# 555LEDBLINK.net
KiCad netlist of a schematic drawn in Altium Designer
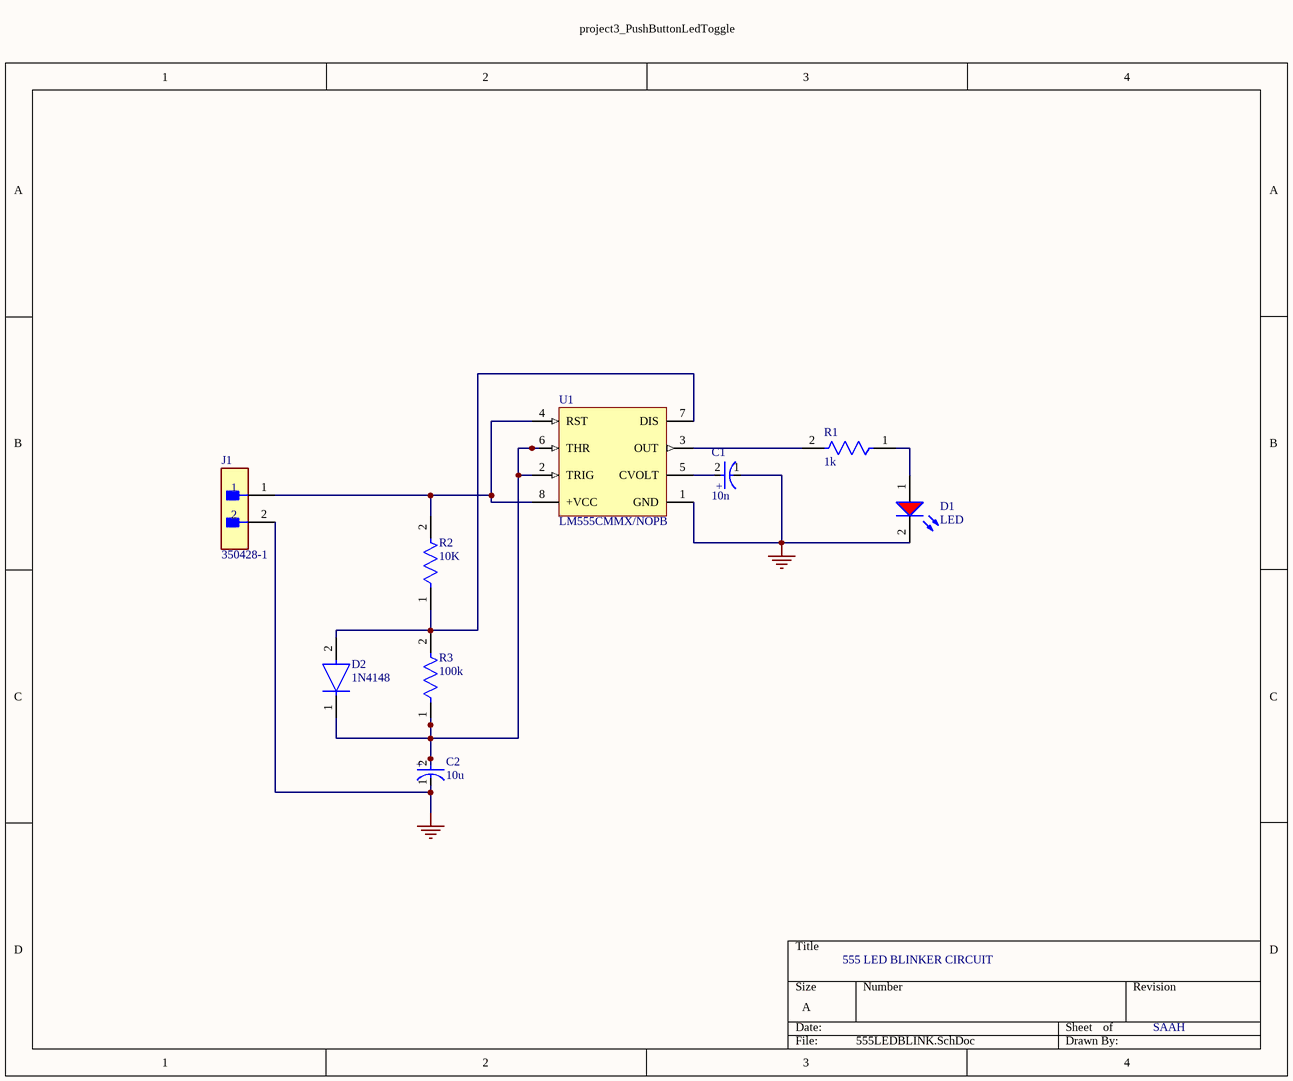
[diagram p0: 555LEDBLINK.SchDoc]

(export (version "E")
  (design (tool "Eeschema 10.0.6"))
  (components
    (comp (ref "C1")
      (value "10n")
      (footprint "FP-RAD-TH-D_12_5_0_5-L_20-MFG")
      (description "Aluminum Electrolytic Capacitors (Radial Lead Type) 10uF ±20% 450V")
      (fields (field (name "TOLERANCE") "20%") (field (name "VOLTAGE") "450V"))
      (libsource (lib "Altium Content Vault") (part "a00bbbee19879c290e62620ae7e47b1"))
    )
    (comp (ref "C2")
      (value "10u")
      (footprint "FP-RAD-TH-D_12_5_0_5-L_20-MFG")
      (description "Aluminum Electrolytic Capacitors (Radial Lead Type) 10uF ±20% 450V")
      (fields (field (name "TOLERANCE") "20%") (field (name "VOLTAGE") "450V"))
      (libsource (lib "Altium Content Vault") (part "a00bbbee19879c290e62620ae7e47b1"))
    )
    (comp (ref "D1")
      (value "LED")
      (footprint "WL-TMRC_D5.9H8.7")
      (description "151051SS04000 WL-TMRC THT Mono-color Round Color")
      (libsource (lib "Altium Content Vault") (part "LED_Red_1A-2K"))
    )
    (comp (ref "D2")
      (value "1N4148")
      (footprint "FP-017AG-MFG")
      (description "DIODE GEN PURP 100V 200MA DO35")
      (fields (field (name "VOLTAGE") "100V"))
      (libsource (lib "Altium Content Vault") (part "d7152d700b627762746794eb795d46e"))
    )
    (comp (ref "J1")
      (value "350428-1")
      (footprint "FP-350428-1-MFG")
      (description "CONN HEADER VERT 2POS 6.35MM")
      (fields
        (field (name "OCTOPART") "https://octopart.com/350428-1-te+connectivity-46505355")
        (field (name "MANUFACTURER") "TE Connectivity")
      )
      (libsource (lib "Altium Content Vault") (part "3bc925449376181038e59eaffc5286c"))
    )
    (comp (ref "R1")
      (value "1k")
      (footprint "FP-CF14-MFG")
      (description "RES 7.5K OHM 1/4W 5% AXIAL")
      (fields (field (name "TOLERANCE") "5%"))
      (libsource (lib "Altium Content Vault") (part "1029c3af85768c4190bb7ad29bc67b5"))
    )
    (comp (ref "R2")
      (value "10K")
      (footprint "FP-CF14-MFG")
      (description "RES 7.5K OHM 1/4W 5% AXIAL")
      (fields (field (name "TOLERANCE") "5%"))
      (libsource (lib "Altium Content Vault") (part "1029c3af85768c4190bb7ad29bc67b5"))
    )
    (comp (ref "R3")
      (value "100k")
      (footprint "FP-CF14-MFG")
      (description "RES 7.5K OHM 1/4W 5% AXIAL")
      (fields (field (name "TOLERANCE") "5%"))
      (libsource (lib "Altium Content Vault") (part "1029c3af85768c4190bb7ad29bc67b5"))
    )
    (comp (ref "U1")
      (value "LM555CMMX/NOPB")
      (footprint "DGK0008A_M")
      (description "Timer, 8-pin Mini SOIC, Pb-Free")
      (fields (field (name "MANUFACTURER") "Texas Instruments"))
      (libsource (lib "Altium Content Vault") (part "AN-TIMER-LM555-8"))
    )
  )
  (nets
    (net (code "1") (name "GND") (class "Default")
      (node (ref "C1") (pin "1") (pinfunction "C_1") (pintype "passive"))
      (node (ref "C2") (pin "1") (pinfunction "C_1") (pintype "passive"))
      (node (ref "D1") (pin "2") (pinfunction "K_2") (pintype "passive"))
      (node (ref "J1") (pin "2") (pinfunction "2_2") (pintype "passive"))
      (node (ref "U1") (pin "1") (pinfunction "GND_1") (pintype "power_in"))
    )
    (net (code "2") (name "Net-(C1-A)") (class "Default")
      (node (ref "C1") (pin "2") (pinfunction "A_2") (pintype "passive"))
      (node (ref "U1") (pin "5") (pinfunction "CVOLT_5") (pintype "passive"))
    )
    (net (code "3") (name "Net-(C2-A)") (class "Default")
      (node (ref "C2") (pin "2") (pinfunction "A_2") (pintype "passive"))
      (node (ref "D2") (pin "1") (pinfunction "C_1") (pintype "passive"))
      (node (ref "R3") (pin "1") (pinfunction "1_1") (pintype "passive"))
      (node (ref "U1") (pin "2") (pinfunction "TRIG_2") (pintype "input"))
      (node (ref "U1") (pin "6") (pinfunction "THR_6") (pintype "input"))
    )
    (net (code "4") (name "Net-(D1-A)") (class "Default")
      (node (ref "D1") (pin "1") (pinfunction "A_1") (pintype "passive"))
      (node (ref "R1") (pin "1") (pinfunction "1_1") (pintype "passive"))
    )
    (net (code "5") (name "Net-(D2-A)") (class "Default")
      (node (ref "D2") (pin "2") (pinfunction "A_2") (pintype "passive"))
      (node (ref "R2") (pin "1") (pinfunction "1_1") (pintype "passive"))
      (node (ref "R3") (pin "2") (pinfunction "2_2") (pintype "passive"))
      (node (ref "U1") (pin "7") (pinfunction "DIS_7") (pintype "open_collector"))
    )
    (net (code "6") (name "Net-(U1-+VCC)") (class "Default")
      (node (ref "J1") (pin "1") (pinfunction "1_1") (pintype "passive"))
      (node (ref "R2") (pin "2") (pinfunction "2_2") (pintype "passive"))
      (node (ref "U1") (pin "4") (pinfunction "RST_4") (pintype "input"))
      (node (ref "U1") (pin "8") (pinfunction "+VCC_8") (pintype "power_in"))
    )
    (net (code "7") (name "Net-(U1-OUT)") (class "Default")
      (node (ref "R1") (pin "2") (pinfunction "2_2") (pintype "passive"))
      (node (ref "U1") (pin "3") (pinfunction "OUT_3") (pintype "output"))
    )
  )
)
